# transmitter.net
KiCad netlist of a schematic drawn in Altium Designer
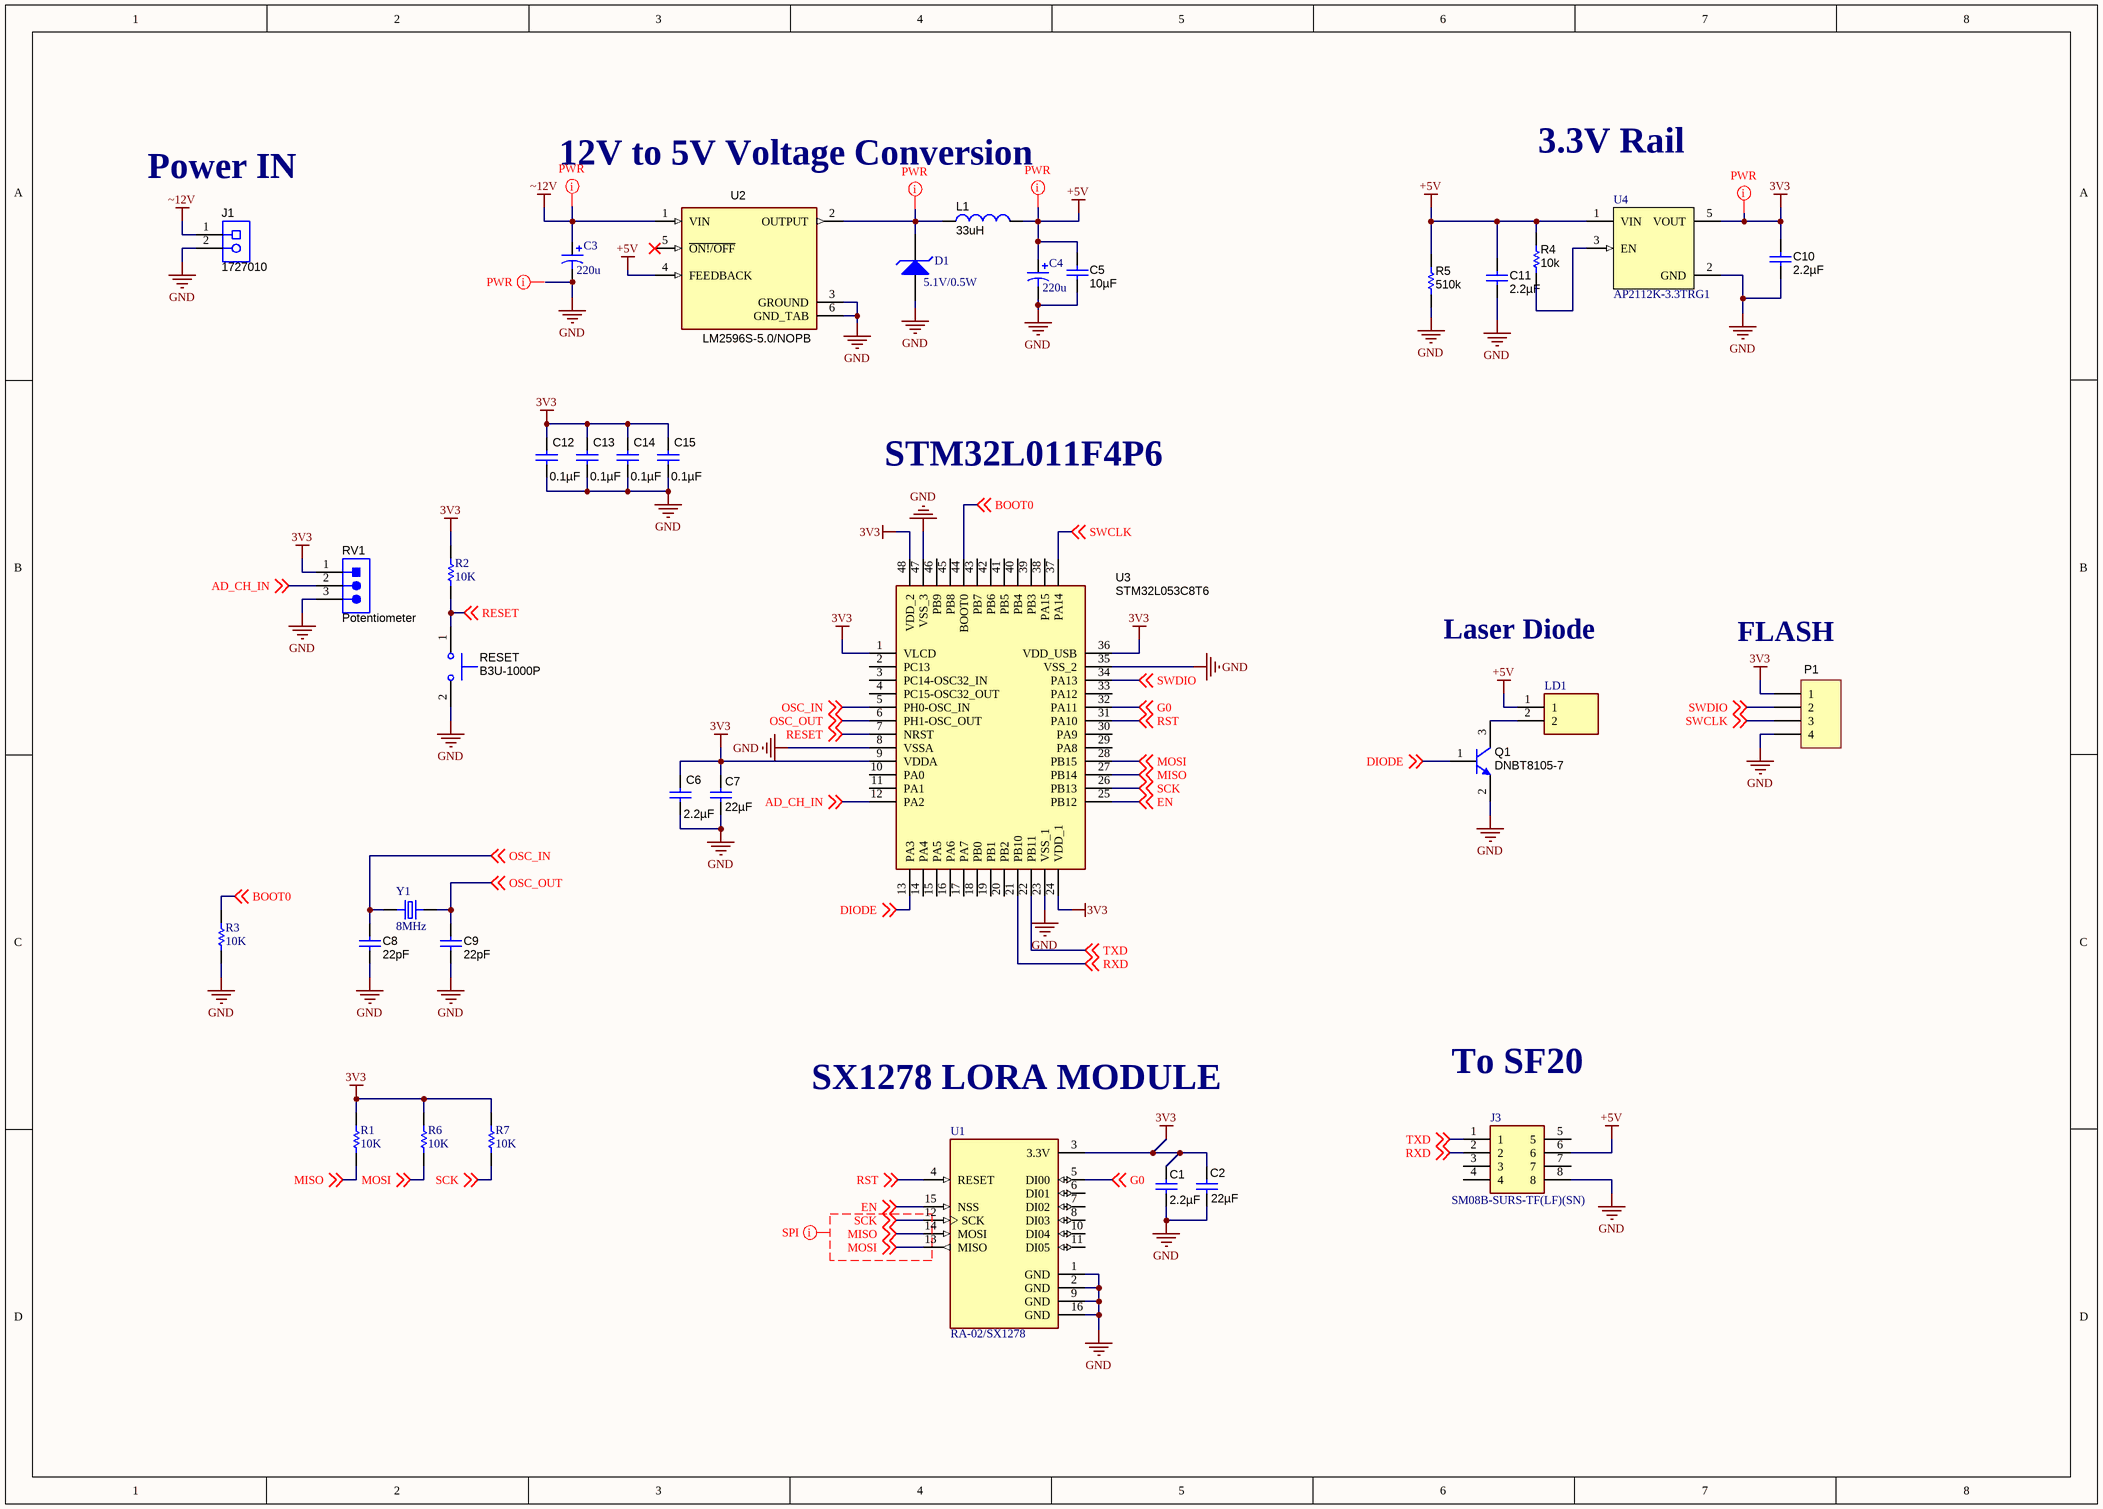
[diagram p0: transmitter.SchDoc]

(export (version "E")
  (design (tool "Eeschema 10.0.6"))
  (components
    (comp (ref "C1")
      (value "C1608X6S1C225K080AC")
      (footprint "0603")
      (description "CAP, CERM, 2.2 µF, 16 V, +/- 10%, X6S, 0603")
      (fields
        (field (name "VALUEDISPLAYED") "2.2µF")
        (field (name "MANUFACTURER") "TDK")
        (field (name "PUBLISHER") "Texas Instruments")
      )
      (libsource (lib "FAMIS") (part "C1608X6S1C225K080AC"))
    )
    (comp (ref "C2")
      (value "C3216X5R1V226M160AC")
      (footprint "1206_180")
      (description "CAP, CERM, 22 µF, 35 V,+/- 20%, X5R, 1206")
      (fields
        (field (name "VALUEDISPLAYED") "22µF")
        (field (name "MANUFACTURER") "TDK")
        (field (name "PUBLISHER") "Texas Instruments")
      )
      (libsource (lib "FAMIS") (part "C3216X5R1V226M160AC"))
    )
    (comp (ref "C3")
      (value "220u")
      (footprint "CAPPRD250W50D630H1120B")
      (description "CAP ALUM 220UF 20% 160V RADIAL")
      (fields
        (field (name "MANUFACTURER") "Nichicon")
        (field (name "MANUFACTURER PART NUMBER") "UCS2C221MHD1TN")
      )
      (libsource (lib "FAMIS") (part "UCS2C221MHD1TN"))
    )
    (comp (ref "C4")
      (value "220u")
      (footprint "CAPPRD250W50D630H1120B")
      (description "CAP ALUM 220UF 20% 160V RADIAL")
      (fields
        (field (name "MANUFACTURER") "Nichicon")
        (field (name "MANUFACTURER PART NUMBER") "UCS2C221MHD1TN")
      )
      (libsource (lib "FAMIS") (part "UCS2C221MHD1TN"))
    )
    (comp (ref "C5")
      (value "EMK212BB7106MG-T")
      (footprint "0805_HV")
      (description "CAP, CERM, 10 µF, 16 V, +/- 20%, X7R, 0805")
      (fields
        (field (name "VALUEDISPLAYED") "10µF")
        (field (name "MANUFACTURER") "Taiyo Yuden")
        (field (name "PUBLISHER") "Texas Instruments")
      )
      (libsource (lib "FAMIS") (part "EMK212BB7106MG-T"))
    )
    (comp (ref "C6")
      (value "C1608X6S1C225K080AC")
      (footprint "0603")
      (description "CAP, CERM, 2.2 µF, 16 V, +/- 10%, X6S, 0603")
      (fields
        (field (name "VALUEDISPLAYED") "2.2µF")
        (field (name "MANUFACTURER") "TDK")
        (field (name "PUBLISHER") "Texas Instruments")
      )
      (libsource (lib "FAMIS") (part "C1608X6S1C225K080AC"))
    )
    (comp (ref "C7")
      (value "C3216X5R1V226M160AC")
      (footprint "1206_180")
      (description "CAP, CERM, 22 µF, 35 V,+/- 20%, X5R, 1206")
      (fields
        (field (name "VALUEDISPLAYED") "22µF")
        (field (name "MANUFACTURER") "TDK")
        (field (name "PUBLISHER") "Texas Instruments")
      )
      (libsource (lib "FAMIS") (part "C3216X5R1V226M160AC"))
    )
    (comp (ref "C8")
      (value "0805YD225KAT2A")
      (footprint "0805_HV")
      (description "CAP, CERM, 2.2 µF, 16 V, +/- 10%, X5R, 0805")
      (fields
        (field (name "VALUEDISPLAYED") "22pF")
        (field (name "MANUFACTURER") "AVX")
        (field (name "PUBLISHER") "Texas Instruments")
      )
      (libsource (lib "FAMIS") (part "0805YD225KAT2A"))
    )
    (comp (ref "C9")
      (value "0805YD225KAT2A")
      (footprint "0805_HV")
      (description "CAP, CERM, 2.2 µF, 16 V, +/- 10%, X5R, 0805")
      (fields
        (field (name "VALUEDISPLAYED") "22pF")
        (field (name "MANUFACTURER") "AVX")
        (field (name "PUBLISHER") "Texas Instruments")
      )
      (libsource (lib "FAMIS") (part "0805YD225KAT2A"))
    )
    (comp (ref "C10")
      (value "0805YD225KAT2A")
      (footprint "0805_HV")
      (description "CAP, CERM, 2.2 µF, 16 V, +/- 10%, X5R, 0805")
      (fields
        (field (name "VALUEDISPLAYED") "2.2µF")
        (field (name "MANUFACTURER") "AVX")
        (field (name "PUBLISHER") "Texas Instruments")
      )
      (libsource (lib "FAMIS") (part "0805YD225KAT2A"))
    )
    (comp (ref "C11")
      (value "0805YD225KAT2A")
      (footprint "0805_HV")
      (description "CAP, CERM, 2.2 µF, 16 V, +/- 10%, X5R, 0805")
      (fields
        (field (name "VALUEDISPLAYED") "2.2µF")
        (field (name "MANUFACTURER") "AVX")
        (field (name "PUBLISHER") "Texas Instruments")
      )
      (libsource (lib "FAMIS") (part "0805YD225KAT2A"))
    )
    (comp (ref "C12")
      (value "C1608X6S1C225K080AC")
      (footprint "0603")
      (description "CAP, CERM, 2.2 µF, 16 V, +/- 10%, X6S, 0603")
      (fields
        (field (name "VALUEDISPLAYED") "0.1µF")
        (field (name "MANUFACTURER") "TDK")
        (field (name "PUBLISHER") "Texas Instruments")
      )
      (libsource (lib "FAMIS") (part "C1608X6S1C225K080AC"))
    )
    (comp (ref "C13")
      (value "C1608X6S1C225K080AC")
      (footprint "0603")
      (description "CAP, CERM, 2.2 µF, 16 V, +/- 10%, X6S, 0603")
      (fields
        (field (name "VALUEDISPLAYED") "0.1µF")
        (field (name "MANUFACTURER") "TDK")
        (field (name "PUBLISHER") "Texas Instruments")
      )
      (libsource (lib "FAMIS") (part "C1608X6S1C225K080AC"))
    )
    (comp (ref "C14")
      (value "C1608X6S1C225K080AC")
      (footprint "0603")
      (description "CAP, CERM, 2.2 µF, 16 V, +/- 10%, X6S, 0603")
      (fields
        (field (name "VALUEDISPLAYED") "0.1µF")
        (field (name "MANUFACTURER") "TDK")
        (field (name "PUBLISHER") "Texas Instruments")
      )
      (libsource (lib "FAMIS") (part "C1608X6S1C225K080AC"))
    )
    (comp (ref "C15")
      (value "C1608X6S1C225K080AC")
      (footprint "0603")
      (description "CAP, CERM, 2.2 µF, 16 V, +/- 10%, X6S, 0603")
      (fields
        (field (name "VALUEDISPLAYED") "0.1µF")
        (field (name "MANUFACTURER") "TDK")
        (field (name "PUBLISHER") "Texas Instruments")
      )
      (libsource (lib "FAMIS") (part "C1608X6S1C225K080AC"))
    )
    (comp (ref "D1")
      (value "5.1V/0.5W")
      (footprint "SOD-123")
      (description "Diode Zener Single 5.1V 5% 500mW 2-Pin SOD-123 T/R")
      (fields
        (field (name "MANUFACTURER") "Diodes")
        (field (name "MANUFACTURER PART NUMBER") "MMSZ5231B-7-F")
      )
      (libsource (lib "FAMIS") (part "5.1V/0.5W zener"))
    )
    (comp (ref "J1")
      (value "1727010")
      (footprint "PhoenixConact_1727010")
      (description "Conn Term Block, 2POS, 3.81mm, TH")
      (fields
        (field (name "MANUFACTURER") "Phoenix Contact")
        (field (name "SYMBOLCREATOR") "a0412235")
        (field (name "PUBLISHER") "Texas Instruments")
      )
      (libsource (lib "FAMIS") (part "1727010"))
    )
    (comp (ref "J3")
      (value "SM08B-SURS-TF(LF)(SN)")
      (footprint "SM08B-SURS-TF")
      (description "CONN HEADER SMD R/A 8POS 0.8MM")
      (fields (field (name "MANUFACTURER") "JST"))
      (libsource (lib "FAMIS") (part "SM08B-SURS-TF(LF)(SN)"))
    )
    (comp (ref "L1")
      (value "33uH")
      (footprint "IND_MSS1210-153MEB")
      (fields
        (field (name "MANUFACTURER") "Coilcraft")
        (field (name "MANUFACTURER PART NUMBER") "MSS1210-105KED")
        (field (name "TOLERANCE") "10%")
      )
      (libsource (lib "FAMIS") (part "MSS1210-333MEB"))
    )
    (comp (ref "LD1")
      (value "Header-2pin(2.5mm)")
      (footprint "B2B-XH-A(LF)(SN)")
      (description "Conn Shrouded Header (4 Sides) HDR 2 POS 2.5mm Solder ST Thru-Hole Box")
      (fields
        (field (name "MANUFACTURER") "JST")
        (field (name "MANUFACTURER PART NUMBER") "B2B-XH-A(LF)(SN)")
      )
      (libsource (lib "FAMIS") (part "B2B-XH-A(LF)(SN)"))
    )
    (comp (ref "P1")
      (value "0901471104")
      (footprint "HDR1X4")
      (description "Conn Socket Strip F 4 POS 2.54mm Solder ST Thru-Hole C-Grid® Tube")
      (fields (field (name "MANUFACTURER") "Molex"))
      (libsource (lib "FAMIS") (part "0901471104"))
    )
    (comp (ref "Q1")
      (value "DNBT8105-7")
      (footprint "SOT-23")
      (description "Transistor, NPN, 60 V, 1 A, AEC-Q101, SOT-23")
      (fields (field (name "MANUFACTURER") "Diodes Inc.") (field (name "PUBLISHER") "Texas Instruments"))
      (libsource (lib "FAMIS") (part "DNBT8105-7, Diodes Inc."))
    )
    (comp (ref "R1")
      (value "10K")
      (footprint "R0805")
      (description "RES SMD 22 OHM 1% 1/8W 0805")
      (fields
        (field (name "MANUFACTURER") "Yageo")
        (field (name "MANUFACTURER PART NUMBER") "RC0805FR-0722RL")
        (field (name ".CREATOR") "MM")
        (field (name ".CHECKED PCB") "RF")
        (field (name ".CHECKED SCH") "RF")
      )
      (libsource (lib "FAMIS") (part "RC0805FR-0722RL"))
    )
    (comp (ref "R2")
      (value "10K")
      (footprint "R0805")
      (description "RES SMD 22 OHM 1% 1/8W 0805")
      (fields
        (field (name "MANUFACTURER") "Yageo")
        (field (name "MANUFACTURER PART NUMBER") "RC0805FR-0722RL")
        (field (name ".CREATOR") "MM")
        (field (name ".CHECKED PCB") "RF")
        (field (name ".CHECKED SCH") "RF")
      )
      (libsource (lib "FAMIS") (part "RC0805FR-0722RL"))
    )
    (comp (ref "R3")
      (value "10K")
      (footprint "R0805")
      (description "RES SMD 22 OHM 1% 1/8W 0805")
      (fields
        (field (name "MANUFACTURER") "Yageo")
        (field (name "MANUFACTURER PART NUMBER") "RC0805FR-0722RL")
        (field (name ".CREATOR") "MM")
        (field (name ".CHECKED PCB") "RF")
        (field (name ".CHECKED SCH") "RF")
      )
      (libsource (lib "FAMIS") (part "RC0805FR-0722RL"))
    )
    (comp (ref "R4")
      (value "CRCW060310K0JNEA")
      (footprint "0603")
      (description "RES, 10 k, 5%, 0.1 W, 0603")
      (fields
        (field (name "MANUFACTURER") "Vishay-Dale")
        (field (name "VALUEDISPLAYED") "10k")
        (field (name "PUBLISHER") "Texas Instruments")
      )
      (libsource (lib "FAMIS") (part "CRCW060310K0JNEA"))
    )
    (comp (ref "R5")
      (value "CRCW0805510KJNEA")
      (footprint "0805_HV")
      (description "RES, 510 k, 5%, 0.125 W, 0805")
      (fields
        (field (name "VALUEDISPLAYED") "510k")
        (field (name "MANUFACTURER") "Vishay-Dale")
        (field (name "PUBLISHER") "Texas Instruments")
      )
      (libsource (lib "FAMIS") (part "CRCW0805510KJNEA"))
    )
    (comp (ref "R6")
      (value "10K")
      (footprint "R0805")
      (description "RES SMD 22 OHM 1% 1/8W 0805")
      (fields
        (field (name "MANUFACTURER") "Yageo")
        (field (name "MANUFACTURER PART NUMBER") "RC0805FR-0722RL")
        (field (name ".CREATOR") "MM")
        (field (name ".CHECKED PCB") "RF")
        (field (name ".CHECKED SCH") "RF")
      )
      (libsource (lib "FAMIS") (part "RC0805FR-0722RL"))
    )
    (comp (ref "R7")
      (value "10K")
      (footprint "R0805")
      (description "RES SMD 22 OHM 1% 1/8W 0805")
      (fields
        (field (name "MANUFACTURER") "Yageo")
        (field (name "MANUFACTURER PART NUMBER") "RC0805FR-0722RL")
        (field (name ".CREATOR") "MM")
        (field (name ".CHECKED PCB") "RF")
        (field (name ".CHECKED SCH") "RF")
      )
      (libsource (lib "FAMIS") (part "RC0805FR-0722RL"))
    )
    (comp (ref "RESET")
      (value "B3U-1000P")
      (footprint "SW_B3U-1000P")
      (description "SWITCH TACTILE SPST-NO 0.05A 12V")
      (fields
        (field (name "MANUFACTURER") "Omron Electronic Components")
        (field (name "SYMBOLCREATOR") "a0412235")
        (field (name "PUBLISHER") "Texas Instruments")
      )
      (libsource (lib "FAMIS") (part "B3U-1000P"))
    )
    (comp (ref "RV1")
      (value "Potentiometer")
      (footprint "WURTH_61300311121")
      (description "Header, 2.54 mm, 3x1, Gold, TH")
      (fields
        (field (name "PARTNUMBER") "61300311121")
        (field (name "MANUFACTURER") "Wurth Elektronik")
        (field (name "SYMBOLCREATOR") "a0799628")
        (field (name "PUBLISHER") "Texas Instruments")
      )
      (libsource (lib "FAMIS") (part "61300311121"))
    )
    (comp (ref "U1")
      (value "RA-02/SX1278")
      (footprint "MODULE_RA-02_LORA")
      (description "LoRA module")
      (libsource (lib "FAMIS") (part "RA-02"))
    )
    (comp (ref "U2")
      (value "LM2596S-5.0/NOPB")
      (footprint "TO170P1524X483-6N")
      (description "Conv DC-DC 4.5V to 40V Inv/Step Down Single-Out 5V 3A 6-Pin(5+Tab) TO-263 Tube")
      (fields (field (name "MANUFACTURER") "TI National Semiconductor"))
      (libsource (lib "FAMIS") (part "LM2596S-5.0/NOPB"))
    )
    (comp (ref "U3")
      (value "STM32L053C8T6")
      (footprint "QFP50P900X900X160-48N")
      (description "IC MCU 32BIT 64KB FLASH 48LQFP")
      (fields (field (name "MANUFACTURER") "STMicroelectronics"))
      (libsource (lib "FAMIS") (part "STM32L053C8T6"))
    )
    (comp (ref "U4")
      (value "AP2112K-3.3TRG1")
      (footprint "SOT95P285X140-5N")
      (description "IC REG LINEAR 3.3V 600MA SOT25")
      (fields (field (name "MANUFACTURER") "Diodes"))
      (libsource (lib "FAMIS") (part "AP2112K-3.3TRG1"))
    )
    (comp (ref "Y1")
      (value "8MHz")
      (footprint "XTAL_ECS-160-20-4XDN")
      (description "Crystals 16.000MHz 30ppm 20pF -40C to 85C")
      (fields (field (name "MANUFACTURER") "TXC") (field (name "MANUFACTURER PART NUMBER") "AS-16.000MAHK-B"))
      (libsource (lib "FAMIS") (part "AS-16.000MAHK-B"))
    )
  )
  (nets
    (net (code "1") (name "+5V") (class "Default")
      (node (ref "C11") (pin "1") (pinfunction "1_1") (pintype "passive"))
      (node (ref "C4") (pin "1") (pinfunction "1_1") (pintype "passive"))
      (node (ref "C5") (pin "1") (pinfunction "1_1") (pintype "passive"))
      (node (ref "J3") (pin "6") (pinfunction "6_6") (pintype "passive"))
      (node (ref "L1") (pin "2") (pinfunction "2_2") (pintype "passive"))
      (node (ref "LD1") (pin "1") (pinfunction "1_1") (pintype "passive"))
      (node (ref "R4") (pin "2") (pinfunction "2_2") (pintype "passive"))
      (node (ref "R5") (pin "2") (pinfunction "2_2") (pintype "passive"))
      (node (ref "U2") (pin "4") (pinfunction "FEEDBACK_4") (pintype "input"))
      (node (ref "U4") (pin "1") (pinfunction "VIN_1") (pintype "power_in"))
    )
    (net (code "2") (name "3V3") (class "Default")
      (node (ref "C1") (pin "1") (pinfunction "1_1") (pintype "passive"))
      (node (ref "C10") (pin "1") (pinfunction "1_1") (pintype "passive"))
      (node (ref "C12") (pin "1") (pinfunction "1_1") (pintype "passive"))
      (node (ref "C13") (pin "1") (pinfunction "1_1") (pintype "passive"))
      (node (ref "C14") (pin "1") (pinfunction "1_1") (pintype "passive"))
      (node (ref "C15") (pin "1") (pinfunction "1_1") (pintype "passive"))
      (node (ref "C2") (pin "1") (pinfunction "1_1") (pintype "passive"))
      (node (ref "C6") (pin "1") (pinfunction "1_1") (pintype "passive"))
      (node (ref "C7") (pin "1") (pinfunction "1_1") (pintype "passive"))
      (node (ref "P1") (pin "1") (pinfunction "1_1") (pintype "passive"))
      (node (ref "R1") (pin "2") (pinfunction "2_2") (pintype "passive"))
      (node (ref "R2") (pin "2") (pinfunction "2_2") (pintype "passive"))
      (node (ref "R6") (pin "2") (pinfunction "2_2") (pintype "passive"))
      (node (ref "R7") (pin "2") (pinfunction "2_2") (pintype "passive"))
      (node (ref "RV1") (pin "1") (pinfunction "1_1") (pintype "passive"))
      (node (ref "U1") (pin "3") (pinfunction "3.3V_3") (pintype "power_in"))
      (node (ref "U3") (pin "1") (pinfunction "VLCD_1") (pintype "passive"))
      (node (ref "U3") (pin "24") (pinfunction "VDD_1_24") (pintype "passive"))
      (node (ref "U3") (pin "36") (pinfunction "VDD_USB_36") (pintype "passive"))
      (node (ref "U3") (pin "48") (pinfunction "VDD_2_48") (pintype "passive"))
      (node (ref "U3") (pin "9") (pinfunction "VDDA_9") (pintype "passive"))
      (node (ref "U4") (pin "5") (pinfunction "VOUT_5") (pintype "power_in"))
    )
    (net (code "3") (name "AD_CH_IN") (class "Default")
      (node (ref "RV1") (pin "2") (pinfunction "2_2") (pintype "passive"))
      (node (ref "U3") (pin "12") (pinfunction "PA2_12") (pintype "passive"))
    )
    (net (code "4") (name "BOOT0") (class "Default")
      (node (ref "R3") (pin "2") (pinfunction "2_2") (pintype "passive"))
      (node (ref "U3") (pin "44") (pinfunction "BOOT0_44") (pintype "passive"))
    )
    (net (code "5") (name "DIODE") (class "Default")
      (node (ref "Q1") (pin "1") (pinfunction "B_1") (pintype "passive"))
      (node (ref "U3") (pin "13") (pinfunction "PA3_13") (pintype "passive"))
    )
    (net (code "6") (name "EN") (class "Default")
      (node (ref "U1") (pin "15") (pinfunction "NSS_15") (pintype "input"))
      (node (ref "U3") (pin "25") (pinfunction "PB12_25") (pintype "passive"))
    )
    (net (code "7") (name "G0") (class "Default")
      (node (ref "U1") (pin "5") (pinfunction "DI00_5") (pintype "bidirectional"))
      (node (ref "U3") (pin "32") (pinfunction "PA11_32") (pintype "passive"))
    )
    (net (code "8") (name "GND") (class "Default")
      (node (ref "C1") (pin "2") (pinfunction "2_2") (pintype "passive"))
      (node (ref "C10") (pin "2") (pinfunction "2_2") (pintype "passive"))
      (node (ref "C11") (pin "2") (pinfunction "2_2") (pintype "passive"))
      (node (ref "C12") (pin "2") (pinfunction "2_2") (pintype "passive"))
      (node (ref "C13") (pin "2") (pinfunction "2_2") (pintype "passive"))
      (node (ref "C14") (pin "2") (pinfunction "2_2") (pintype "passive"))
      (node (ref "C15") (pin "2") (pinfunction "2_2") (pintype "passive"))
      (node (ref "C2") (pin "2") (pinfunction "2_2") (pintype "passive"))
      (node (ref "C3") (pin "2") (pinfunction "2_2") (pintype "passive"))
      (node (ref "C4") (pin "2") (pinfunction "2_2") (pintype "passive"))
      (node (ref "C5") (pin "2") (pinfunction "2_2") (pintype "passive"))
      (node (ref "C6") (pin "2") (pinfunction "2_2") (pintype "passive"))
      (node (ref "C7") (pin "2") (pinfunction "2_2") (pintype "passive"))
      (node (ref "C8") (pin "2") (pinfunction "2_2") (pintype "passive"))
      (node (ref "C9") (pin "2") (pinfunction "2_2") (pintype "passive"))
      (node (ref "D1") (pin "1") (pinfunction "A_1") (pintype "passive"))
      (node (ref "J1") (pin "2") (pinfunction "2_2") (pintype "passive"))
      (node (ref "J3") (pin "8") (pinfunction "8_8") (pintype "passive"))
      (node (ref "P1") (pin "4") (pinfunction "4_4") (pintype "passive"))
      (node (ref "Q1") (pin "2") (pinfunction "E_2") (pintype "passive"))
      (node (ref "R3") (pin "1") (pinfunction "1_1") (pintype "passive"))
      (node (ref "R5") (pin "1") (pinfunction "1_1") (pintype "passive"))
      (node (ref "RESET") (pin "2") (pinfunction "2_2") (pintype "passive"))
      (node (ref "RV1") (pin "3") (pinfunction "3_3") (pintype "passive"))
      (node (ref "U1") (pin "1") (pinfunction "GND_1") (pintype "power_in"))
      (node (ref "U1") (pin "16") (pinfunction "GND_16") (pintype "power_in"))
      (node (ref "U1") (pin "2") (pinfunction "GND_2") (pintype "power_in"))
      (node (ref "U1") (pin "9") (pinfunction "GND_9") (pintype "power_in"))
      (node (ref "U2") (pin "3") (pinfunction "GROUND_3") (pintype "power_in"))
      (node (ref "U2") (pin "6") (pinfunction "GND_TAB_6") (pintype "power_in"))
      (node (ref "U3") (pin "23") (pinfunction "VSS_1_23") (pintype "passive"))
      (node (ref "U3") (pin "35") (pinfunction "VSS_2_35") (pintype "passive"))
      (node (ref "U3") (pin "47") (pinfunction "VSS_3_47") (pintype "passive"))
      (node (ref "U3") (pin "8") (pinfunction "VSSA_8") (pintype "passive"))
      (node (ref "U4") (pin "2") (pinfunction "GND_2") (pintype "power_in"))
    )
    (net (code "9") (name "MISO") (class "Default")
      (node (ref "R1") (pin "1") (pinfunction "1_1") (pintype "passive"))
      (node (ref "U1") (pin "14") (pinfunction "MOSI_14") (pintype "input"))
      (node (ref "U3") (pin "27") (pinfunction "PB14_27") (pintype "passive"))
    )
    (net (code "10") (name "MOSI") (class "Default")
      (node (ref "R6") (pin "1") (pinfunction "1_1") (pintype "passive"))
      (node (ref "U1") (pin "13") (pinfunction "MISO_13") (pintype "output"))
      (node (ref "U3") (pin "28") (pinfunction "PB15_28") (pintype "passive"))
    )
    (net (code "11") (name "Net-(D1-K)") (class "Default")
      (node (ref "D1") (pin "2") (pinfunction "K_2") (pintype "passive"))
      (node (ref "L1") (pin "1") (pinfunction "1_1") (pintype "passive"))
      (node (ref "U2") (pin "2") (pinfunction "OUTPUT_2") (pintype "output"))
    )
    (net (code "12") (name "Net-(Q1-C)") (class "Default")
      (node (ref "LD1") (pin "2") (pinfunction "2_2") (pintype "passive"))
      (node (ref "Q1") (pin "3") (pinfunction "C_3") (pintype "passive"))
    )
    (net (code "13") (name "Net-(U4-EN)") (class "Default")
      (node (ref "R4") (pin "1") (pinfunction "1_1") (pintype "passive"))
      (node (ref "U4") (pin "3") (pinfunction "EN_3") (pintype "input"))
    )
    (net (code "14") (name "OSC_IN") (class "Default")
      (node (ref "C8") (pin "1") (pinfunction "1_1") (pintype "passive"))
      (node (ref "U3") (pin "5") (pinfunction "PH0-OSC_IN_5") (pintype "passive"))
      (node (ref "Y1") (pin "1") (pinfunction "1_1") (pintype "passive"))
    )
    (net (code "15") (name "OSC_OUT") (class "Default")
      (node (ref "C9") (pin "1") (pinfunction "1_1") (pintype "passive"))
      (node (ref "U3") (pin "6") (pinfunction "PH1-OSC_OUT_6") (pintype "passive"))
      (node (ref "Y1") (pin "2") (pinfunction "2_2") (pintype "passive"))
    )
    (net (code "16") (name "RESET") (class "Default")
      (node (ref "R2") (pin "1") (pinfunction "1_1") (pintype "passive"))
      (node (ref "RESET") (pin "1") (pinfunction "1_1") (pintype "passive"))
      (node (ref "U3") (pin "7") (pinfunction "NRST_7") (pintype "passive"))
    )
    (net (code "17") (name "RST") (class "Default")
      (node (ref "U1") (pin "4") (pinfunction "RESET_4") (pintype "input"))
      (node (ref "U3") (pin "31") (pinfunction "PA10_31") (pintype "passive"))
    )
    (net (code "18") (name "RXD") (class "Default")
      (node (ref "J3") (pin "2") (pinfunction "2_2") (pintype "passive"))
      (node (ref "U3") (pin "21") (pinfunction "PB10_21") (pintype "passive"))
    )
    (net (code "19") (name "SCK") (class "Default")
      (node (ref "R7") (pin "1") (pinfunction "1_1") (pintype "passive"))
      (node (ref "U1") (pin "12") (pinfunction "SCK_12") (pintype "input"))
      (node (ref "U3") (pin "26") (pinfunction "PB13_26") (pintype "passive"))
    )
    (net (code "20") (name "SWCLK") (class "Default")
      (node (ref "P1") (pin "3") (pinfunction "3_3") (pintype "passive"))
      (node (ref "U3") (pin "37") (pinfunction "PA14_37") (pintype "passive"))
    )
    (net (code "21") (name "SWDIO") (class "Default")
      (node (ref "P1") (pin "2") (pinfunction "2_2") (pintype "passive"))
      (node (ref "U3") (pin "34") (pinfunction "PA13_34") (pintype "passive"))
    )
    (net (code "22") (name "TXD") (class "Default")
      (node (ref "J3") (pin "1") (pinfunction "1_1") (pintype "passive"))
      (node (ref "U3") (pin "22") (pinfunction "PB11_22") (pintype "passive"))
    )
    (net (code "23") (name "unconnected-(J3-Pad3)") (class "Default")
      (node (ref "J3") (pin "3") (pinfunction "3_3") (pintype "passive"))
    )
    (net (code "24") (name "unconnected-(J3-Pad4)") (class "Default")
      (node (ref "J3") (pin "4") (pinfunction "4_4") (pintype "passive"))
    )
    (net (code "25") (name "unconnected-(J3-Pad5)") (class "Default")
      (node (ref "J3") (pin "5") (pinfunction "5_5") (pintype "passive"))
    )
    (net (code "26") (name "unconnected-(J3-Pad7)") (class "Default")
      (node (ref "J3") (pin "7") (pinfunction "7_7") (pintype "passive"))
    )
    (net (code "27") (name "unconnected-(U1-DI01-Pad6)") (class "Default")
      (node (ref "U1") (pin "6") (pinfunction "DI01_6") (pintype "bidirectional"))
    )
    (net (code "28") (name "unconnected-(U1-DI02-Pad7)") (class "Default")
      (node (ref "U1") (pin "7") (pinfunction "DI02_7") (pintype "bidirectional"))
    )
    (net (code "29") (name "unconnected-(U1-DI03-Pad8)") (class "Default")
      (node (ref "U1") (pin "8") (pinfunction "DI03_8") (pintype "bidirectional"))
    )
    (net (code "30") (name "unconnected-(U1-DI04-Pad10)") (class "Default")
      (node (ref "U1") (pin "10") (pinfunction "DI04_10") (pintype "bidirectional"))
    )
    (net (code "31") (name "unconnected-(U1-DI05-Pad11)") (class "Default")
      (node (ref "U1") (pin "11") (pinfunction "DI05_11") (pintype "bidirectional"))
    )
    (net (code "32") (name "unconnected-(U2-~{ON!{slash}OFF}-Pad5)") (class "Default")
      (node (ref "U2") (pin "5") (pinfunction "~{ON!/OFF}_5") (pintype "input+no_connect"))
    )
    (net (code "33") (name "unconnected-(U3-PA0-Pad10)") (class "Default")
      (node (ref "U3") (pin "10") (pinfunction "PA0_10") (pintype "passive"))
    )
    (net (code "34") (name "unconnected-(U3-PA1-Pad11)") (class "Default")
      (node (ref "U3") (pin "11") (pinfunction "PA1_11") (pintype "passive"))
    )
    (net (code "35") (name "unconnected-(U3-PA4-Pad14)") (class "Default")
      (node (ref "U3") (pin "14") (pinfunction "PA4_14") (pintype "passive"))
    )
    (net (code "36") (name "unconnected-(U3-PA5-Pad15)") (class "Default")
      (node (ref "U3") (pin "15") (pinfunction "PA5_15") (pintype "passive"))
    )
    (net (code "37") (name "unconnected-(U3-PA6-Pad16)") (class "Default")
      (node (ref "U3") (pin "16") (pinfunction "PA6_16") (pintype "passive"))
    )
    (net (code "38") (name "unconnected-(U3-PA7-Pad17)") (class "Default")
      (node (ref "U3") (pin "17") (pinfunction "PA7_17") (pintype "passive"))
    )
    (net (code "39") (name "unconnected-(U3-PA8-Pad29)") (class "Default")
      (node (ref "U3") (pin "29") (pinfunction "PA8_29") (pintype "passive"))
    )
    (net (code "40") (name "unconnected-(U3-PA9-Pad30)") (class "Default")
      (node (ref "U3") (pin "30") (pinfunction "PA9_30") (pintype "passive"))
    )
    (net (code "41") (name "unconnected-(U3-PA12-Pad33)") (class "Default")
      (node (ref "U3") (pin "33") (pinfunction "PA12_33") (pintype "passive"))
    )
    (net (code "42") (name "unconnected-(U3-PA15-Pad38)") (class "Default")
      (node (ref "U3") (pin "38") (pinfunction "PA15_38") (pintype "passive"))
    )
    (net (code "43") (name "unconnected-(U3-PB0-Pad18)") (class "Default")
      (node (ref "U3") (pin "18") (pinfunction "PB0_18") (pintype "passive"))
    )
    (net (code "44") (name "unconnected-(U3-PB1-Pad19)") (class "Default")
      (node (ref "U3") (pin "19") (pinfunction "PB1_19") (pintype "passive"))
    )
    (net (code "45") (name "unconnected-(U3-PB2-Pad20)") (class "Default")
      (node (ref "U3") (pin "20") (pinfunction "PB2_20") (pintype "passive"))
    )
    (net (code "46") (name "unconnected-(U3-PB3-Pad39)") (class "Default")
      (node (ref "U3") (pin "39") (pinfunction "PB3_39") (pintype "passive"))
    )
    (net (code "47") (name "unconnected-(U3-PB4-Pad40)") (class "Default")
      (node (ref "U3") (pin "40") (pinfunction "PB4_40") (pintype "passive"))
    )
    (net (code "48") (name "unconnected-(U3-PB5-Pad41)") (class "Default")
      (node (ref "U3") (pin "41") (pinfunction "PB5_41") (pintype "passive"))
    )
    (net (code "49") (name "unconnected-(U3-PB6-Pad42)") (class "Default")
      (node (ref "U3") (pin "42") (pinfunction "PB6_42") (pintype "passive"))
    )
    (net (code "50") (name "unconnected-(U3-PB7-Pad43)") (class "Default")
      (node (ref "U3") (pin "43") (pinfunction "PB7_43") (pintype "passive"))
    )
    (net (code "51") (name "unconnected-(U3-PB8-Pad45)") (class "Default")
      (node (ref "U3") (pin "45") (pinfunction "PB8_45") (pintype "passive"))
    )
    (net (code "52") (name "unconnected-(U3-PB9-Pad46)") (class "Default")
      (node (ref "U3") (pin "46") (pinfunction "PB9_46") (pintype "passive"))
    )
    (net (code "53") (name "unconnected-(U3-PC13-Pad2)") (class "Default")
      (node (ref "U3") (pin "2") (pinfunction "PC13_2") (pintype "passive"))
    )
    (net (code "54") (name "unconnected-(U3-PC14-OSC32_IN-Pad3)") (class "Default")
      (node (ref "U3") (pin "3") (pinfunction "PC14-OSC32_IN_3") (pintype "passive"))
    )
    (net (code "55") (name "unconnected-(U3-PC15-OSC32_OUT-Pad4)") (class "Default")
      (node (ref "U3") (pin "4") (pinfunction "PC15-OSC32_OUT_4") (pintype "passive"))
    )
    (net (code "56") (name "~12V") (class "Default")
      (node (ref "C3") (pin "1") (pinfunction "1_1") (pintype "passive"))
      (node (ref "J1") (pin "1") (pinfunction "1_1") (pintype "passive"))
      (node (ref "U2") (pin "1") (pinfunction "VIN_1") (pintype "input"))
    )
  )
)
